# moth_v3_60mm_v3_0.net
KiCad netlist of a schematic drawn in EAGLE
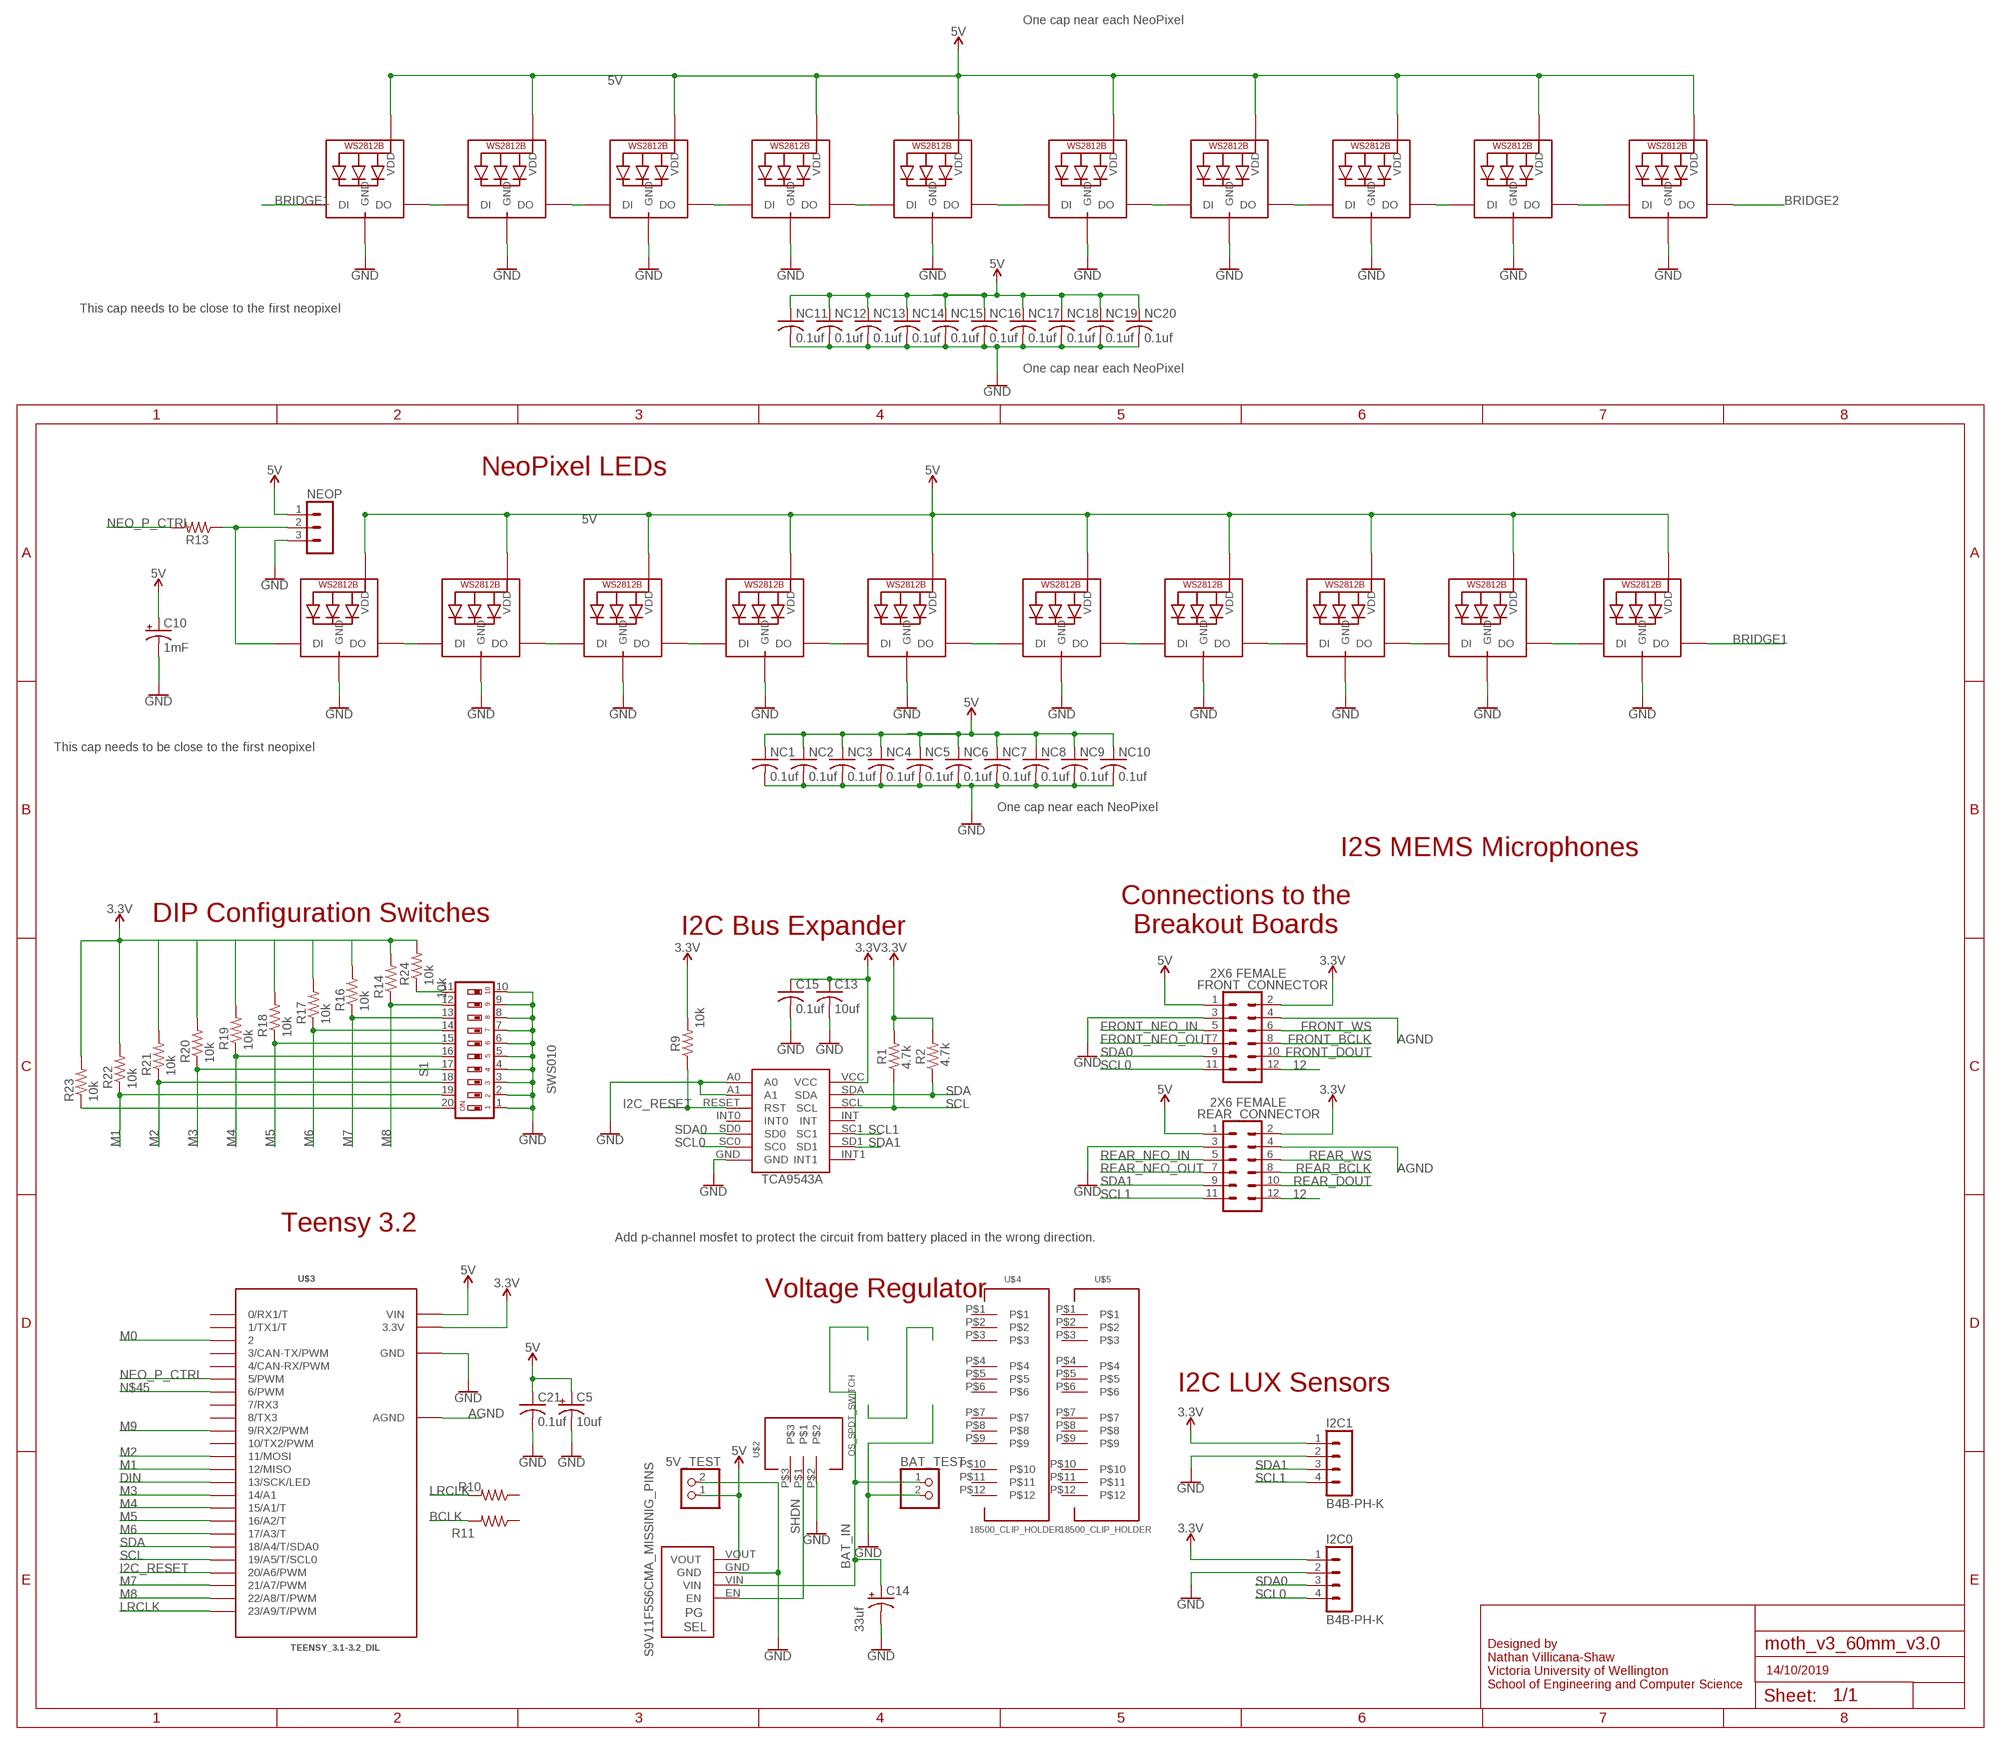
[diagram p0: schematic, sheet 1]

(export (version "E")
  (design (tool "Eeschema 10.0.6"))
  (components
    (comp (ref "5V_TEST")
      (value "PINHD-1X2")
      (footprint "eagle-import:1X02")
      (libsource (lib "eagle-import") (part "PINHD-1X2"))
    )
    (comp (ref "BAT_TEST")
      (value "PINHD-1X2")
      (footprint "eagle-import:1X02")
      (libsource (lib "eagle-import") (part "PINHD-1X2"))
    )
    (comp (ref "C5")
      (value "10uf")
      (footprint "eagle-import:E2,5-6")
      (libsource (lib "eagle-import") (part "CPOL-USE2.5-6"))
    )
    (comp (ref "C10")
      (value "1mF")
      (footprint "eagle-import:CPOL-RADIAL-5MM-10MM")
      (libsource (lib "eagle-import") (part "1000UF-RADIAL-5MM-25V-20%"))
    )
    (comp (ref "C13")
      (value "10uf")
      (footprint "eagle-import:C1206K")
      (libsource (lib "eagle-import") (part "C-USC1206K"))
    )
    (comp (ref "C14")
      (value "33uf")
      (footprint "eagle-import:E2-5")
      (libsource (lib "eagle-import") (part "CPOL-USE2-5"))
    )
    (comp (ref "C15")
      (value "0.1uf")
      (footprint "eagle-import:C1206K")
      (libsource (lib "eagle-import") (part "C-USC1206K"))
    )
    (comp (ref "C21")
      (value "0.1uf")
      (footprint "eagle-import:C1206K")
      (libsource (lib "eagle-import") (part "C-USC1206K"))
    )
    (comp (ref "FRONT_CONNECTOR")
      (value "2X6 FEMALE")
      (footprint "eagle-import:2X6")
      (libsource (lib "eagle-import") (part "CONN_06X2PTH_FEMALE"))
    )
    (comp (ref "I2C0")
      (value "B4B-PH-K")
      (footprint "eagle-import:B4B-PH-K")
      (libsource (lib "eagle-import") (part "B4B-PH-K"))
    )
    (comp (ref "I2C1")
      (value "B4B-PH-K")
      (footprint "eagle-import:B4B-PH-K")
      (libsource (lib "eagle-import") (part "B4B-PH-K"))
    )
    (comp (ref "NC1")
      (value "0.1uf")
      (footprint "eagle-import:C1206K")
      (libsource (lib "eagle-import") (part "C-USC1206K"))
    )
    (comp (ref "NC2")
      (value "0.1uf")
      (footprint "eagle-import:C1206K")
      (libsource (lib "eagle-import") (part "C-USC1206K"))
    )
    (comp (ref "NC3")
      (value "0.1uf")
      (footprint "eagle-import:C1206K")
      (libsource (lib "eagle-import") (part "C-USC1206K"))
    )
    (comp (ref "NC4")
      (value "0.1uf")
      (footprint "eagle-import:C1206K")
      (libsource (lib "eagle-import") (part "C-USC1206K"))
    )
    (comp (ref "NC5")
      (value "0.1uf")
      (footprint "eagle-import:C1206K")
      (libsource (lib "eagle-import") (part "C-USC1206K"))
    )
    (comp (ref "NC6")
      (value "0.1uf")
      (footprint "eagle-import:C1206K")
      (libsource (lib "eagle-import") (part "C-USC1206K"))
    )
    (comp (ref "NC7")
      (value "0.1uf")
      (footprint "eagle-import:C1206K")
      (libsource (lib "eagle-import") (part "C-USC1206K"))
    )
    (comp (ref "NC8")
      (value "0.1uf")
      (footprint "eagle-import:C1206K")
      (libsource (lib "eagle-import") (part "C-USC1206K"))
    )
    (comp (ref "NC9")
      (value "0.1uf")
      (footprint "eagle-import:C1206K")
      (libsource (lib "eagle-import") (part "C-USC1206K"))
    )
    (comp (ref "NC10")
      (value "0.1uf")
      (footprint "eagle-import:C1206K")
      (libsource (lib "eagle-import") (part "C-USC1206K"))
    )
    (comp (ref "NC11")
      (value "0.1uf")
      (footprint "eagle-import:C1206K")
      (libsource (lib "eagle-import") (part "C-USC1206K"))
    )
    (comp (ref "NC12")
      (value "0.1uf")
      (footprint "eagle-import:C1206K")
      (libsource (lib "eagle-import") (part "C-USC1206K"))
    )
    (comp (ref "NC13")
      (value "0.1uf")
      (footprint "eagle-import:C1206K")
      (libsource (lib "eagle-import") (part "C-USC1206K"))
    )
    (comp (ref "NC14")
      (value "0.1uf")
      (footprint "eagle-import:C1206K")
      (libsource (lib "eagle-import") (part "C-USC1206K"))
    )
    (comp (ref "NC15")
      (value "0.1uf")
      (footprint "eagle-import:C1206K")
      (libsource (lib "eagle-import") (part "C-USC1206K"))
    )
    (comp (ref "NC16")
      (value "0.1uf")
      (footprint "eagle-import:C1206K")
      (libsource (lib "eagle-import") (part "C-USC1206K"))
    )
    (comp (ref "NC17")
      (value "0.1uf")
      (footprint "eagle-import:C1206K")
      (libsource (lib "eagle-import") (part "C-USC1206K"))
    )
    (comp (ref "NC18")
      (value "0.1uf")
      (footprint "eagle-import:C1206K")
      (libsource (lib "eagle-import") (part "C-USC1206K"))
    )
    (comp (ref "NC19")
      (value "0.1uf")
      (footprint "eagle-import:C1206K")
      (libsource (lib "eagle-import") (part "C-USC1206K"))
    )
    (comp (ref "NC20")
      (value "0.1uf")
      (footprint "eagle-import:C1206K")
      (libsource (lib "eagle-import") (part "C-USC1206K"))
    )
    (comp (ref "NEO1")
      (value "WS2812B5050")
      (footprint "eagle-import:WS2812B")
      (libsource (lib "eagle-import") (part "WS2812B5050"))
    )
    (comp (ref "NEO2")
      (value "WS2812B5050")
      (footprint "eagle-import:WS2812B")
      (libsource (lib "eagle-import") (part "WS2812B5050"))
    )
    (comp (ref "NEO3")
      (value "WS2812B5050")
      (footprint "eagle-import:WS2812B")
      (libsource (lib "eagle-import") (part "WS2812B5050"))
    )
    (comp (ref "NEO4")
      (value "WS2812B5050")
      (footprint "eagle-import:WS2812B")
      (libsource (lib "eagle-import") (part "WS2812B5050"))
    )
    (comp (ref "NEO5")
      (value "WS2812B5050")
      (footprint "eagle-import:WS2812B")
      (libsource (lib "eagle-import") (part "WS2812B5050"))
    )
    (comp (ref "NEO6")
      (value "WS2812B5050")
      (footprint "eagle-import:WS2812B")
      (libsource (lib "eagle-import") (part "WS2812B5050"))
    )
    (comp (ref "NEO7")
      (value "WS2812B5050")
      (footprint "eagle-import:WS2812B")
      (libsource (lib "eagle-import") (part "WS2812B5050"))
    )
    (comp (ref "NEO8")
      (value "WS2812B5050")
      (footprint "eagle-import:WS2812B")
      (libsource (lib "eagle-import") (part "WS2812B5050"))
    )
    (comp (ref "NEO9")
      (value "WS2812B5050")
      (footprint "eagle-import:WS2812B")
      (libsource (lib "eagle-import") (part "WS2812B5050"))
    )
    (comp (ref "NEO10")
      (value "WS2812B5050")
      (footprint "eagle-import:WS2812B")
      (libsource (lib "eagle-import") (part "WS2812B5050"))
    )
    (comp (ref "NEO11")
      (value "WS2812B5050")
      (footprint "eagle-import:WS2812B")
      (libsource (lib "eagle-import") (part "WS2812B5050"))
    )
    (comp (ref "NEO12")
      (value "WS2812B5050")
      (footprint "eagle-import:WS2812B")
      (libsource (lib "eagle-import") (part "WS2812B5050"))
    )
    (comp (ref "NEO13")
      (value "WS2812B5050")
      (footprint "eagle-import:WS2812B")
      (libsource (lib "eagle-import") (part "WS2812B5050"))
    )
    (comp (ref "NEO14")
      (value "WS2812B5050")
      (footprint "eagle-import:WS2812B")
      (libsource (lib "eagle-import") (part "WS2812B5050"))
    )
    (comp (ref "NEO15")
      (value "WS2812B5050")
      (footprint "eagle-import:WS2812B")
      (libsource (lib "eagle-import") (part "WS2812B5050"))
    )
    (comp (ref "NEO16")
      (value "WS2812B5050")
      (footprint "eagle-import:WS2812B")
      (libsource (lib "eagle-import") (part "WS2812B5050"))
    )
    (comp (ref "NEO17")
      (value "WS2812B5050")
      (footprint "eagle-import:WS2812B")
      (libsource (lib "eagle-import") (part "WS2812B5050"))
    )
    (comp (ref "NEO18")
      (value "WS2812B5050")
      (footprint "eagle-import:WS2812B")
      (libsource (lib "eagle-import") (part "WS2812B5050"))
    )
    (comp (ref "NEO19")
      (value "WS2812B5050")
      (footprint "eagle-import:WS2812B")
      (libsource (lib "eagle-import") (part "WS2812B5050"))
    )
    (comp (ref "NEO20")
      (value "WS2812B5050")
      (footprint "eagle-import:WS2812B")
      (libsource (lib "eagle-import") (part "WS2812B5050"))
    )
    (comp (ref "NEOP")
      (value "B3B-PH-K")
      (footprint "eagle-import:B3B-PH-K")
      (libsource (lib "eagle-import") (part "B3B-PH-K"))
    )
    (comp (ref "R1")
      (value "4.7k")
      (footprint "eagle-import:R1206W")
      (libsource (lib "eagle-import") (part "R-US_R1206W"))
    )
    (comp (ref "R2")
      (value "4.7k")
      (footprint "eagle-import:R1206W")
      (libsource (lib "eagle-import") (part "R-US_R1206W"))
    )
    (comp (ref "R9")
      (value "10k")
      (footprint "eagle-import:R1206W")
      (libsource (lib "eagle-import") (part "R-US_R1206W"))
    )
    (comp (ref "R10")
      (value "68R")
      (footprint "eagle-import:M1206")
      (libsource (lib "eagle-import") (part "R-US_M1206"))
    )
    (comp (ref "R11")
      (value "68R")
      (footprint "eagle-import:M1206")
      (libsource (lib "eagle-import") (part "R-US_M1206"))
    )
    (comp (ref "R13")
      (value "300 R")
      (footprint "eagle-import:R1206W")
      (libsource (lib "eagle-import") (part "R-US_R1206W"))
    )
    (comp (ref "R14")
      (value "10k")
      (footprint "eagle-import:R1206W")
      (libsource (lib "eagle-import") (part "R-US_R1206W"))
    )
    (comp (ref "R16")
      (value "10k")
      (footprint "eagle-import:R1206W")
      (libsource (lib "eagle-import") (part "R-US_R1206W"))
    )
    (comp (ref "R17")
      (value "10k")
      (footprint "eagle-import:R1206W")
      (libsource (lib "eagle-import") (part "R-US_R1206W"))
    )
    (comp (ref "R18")
      (value "10k")
      (footprint "eagle-import:R1206W")
      (libsource (lib "eagle-import") (part "R-US_R1206W"))
    )
    (comp (ref "R19")
      (value "10k")
      (footprint "eagle-import:R1206W")
      (libsource (lib "eagle-import") (part "R-US_R1206W"))
    )
    (comp (ref "R20")
      (value "10k")
      (footprint "eagle-import:R1206W")
      (libsource (lib "eagle-import") (part "R-US_R1206W"))
    )
    (comp (ref "R21")
      (value "10k")
      (footprint "eagle-import:R1206W")
      (libsource (lib "eagle-import") (part "R-US_R1206W"))
    )
    (comp (ref "R22")
      (value "10k")
      (footprint "eagle-import:R1206W")
      (libsource (lib "eagle-import") (part "R-US_R1206W"))
    )
    (comp (ref "R23")
      (value "10k")
      (footprint "eagle-import:R1206W")
      (libsource (lib "eagle-import") (part "R-US_R1206W"))
    )
    (comp (ref "R24")
      (value "10k")
      (footprint "eagle-import:R1206W")
      (libsource (lib "eagle-import") (part "R-US_R1206W"))
    )
    (comp (ref "REAR_CONNECTOR")
      (value "2X6 FEMALE")
      (footprint "eagle-import:2X6")
      (libsource (lib "eagle-import") (part "CONN_06X2PTH_FEMALE"))
    )
    (comp (ref "S1")
      (value "SWS010")
      (footprint "eagle-import:SMS-010")
      (libsource (lib "eagle-import") (part "SWS010"))
    )
    (comp (ref "U$1")
      (value "TCA9543A")
      (footprint "eagle-import:SO14")
      (libsource (lib "eagle-import") (part "TCA9543A"))
    )
    (comp (ref "U$2")
      (value "OS_SPDT_SWITCH")
      (footprint "eagle-import:OS_SPDT_SLIDE_SWITCH")
      (libsource (lib "eagle-import") (part "OS_SPDT_SWITCH"))
    )
    (comp (ref "U$3")
      (value "TEENSY_3.1-3.2_DIL")
      (footprint "eagle-import:TEENSY_3.0-3.2&LC_DIL")
      (libsource (lib "eagle-import") (part "TEENSY_3.1-3.2_DIL"))
    )
    (comp (ref "U$4")
      (value "18500_CLIP_HOLDER")
      (footprint "eagle-import:3PINBATTERY_CLIP")
      (libsource (lib "eagle-import") (part "18500_CLIP_HOLDER"))
    )
    (comp (ref "U$5")
      (value "18500_CLIP_HOLDER")
      (footprint "eagle-import:3PINBATTERY_CLIP")
      (libsource (lib "eagle-import") (part "18500_CLIP_HOLDER"))
    )
    (comp (ref "U$6")
      (value "S9V11F5S6CMA_MISSINIG_PINS")
      (footprint "eagle-import:S9V11F3S5CMA_MISSING_PINS")
      (libsource (lib "eagle-import") (part "S9V11F5S6CMA_MISSINIG_PINS"))
    )
  )
  (nets
    (net (code "1") (name "/12") (class "Default")
      (node (ref "FRONT_CONNECTOR") (pin "12") (pinfunction "12_12") (pintype "passive"))
      (node (ref "REAR_CONNECTOR") (pin "12") (pinfunction "12_12") (pintype "passive"))
    )
    (net (code "2") (name "/AGND") (class "Default")
      (node (ref "FRONT_CONNECTOR") (pin "4") (pinfunction "4_4") (pintype "passive"))
      (node (ref "REAR_CONNECTOR") (pin "4") (pinfunction "4_4") (pintype "passive"))
      (node (ref "U$3") (pin "AGND") (pinfunction "AGND_AGND") (pintype "power_in"))
    )
    (net (code "3") (name "/BAT_IN") (class "Default")
      (node (ref "BAT_TEST") (pin "1") (pinfunction "1_1") (pintype "passive"))
      (node (ref "C14") (pin "+") (pinfunction "+_+") (pintype "passive"))
      (node (ref "U$6") (pin "VIN") (pinfunction "VIN_VIN") (pintype "bidirectional"))
    )
    (net (code "4") (name "/BCLK") (class "Default")
      (node (ref "R11") (pin "2") (pinfunction "2_2") (pintype "passive"))
    )
    (net (code "5") (name "/BRIDGE1") (class "Default")
      (node (ref "NEO10") (pin "2-DOUT") (pinfunction "DO_2-DOUT") (pintype "output"))
      (node (ref "NEO14") (pin "4-DIN") (pinfunction "DI_4-DIN") (pintype "input"))
    )
    (net (code "6") (name "/BRIDGE2") (class "Default")
      (node (ref "NEO20") (pin "2-DOUT") (pinfunction "DO_2-DOUT") (pintype "output"))
    )
    (net (code "7") (name "/DIN") (class "Default")
      (node (ref "U$3") (pin "13") (pinfunction "13/SCK/LED_13") (pintype "bidirectional"))
    )
    (net (code "8") (name "/FRONT_BCLK") (class "Default")
      (node (ref "FRONT_CONNECTOR") (pin "8") (pinfunction "8_8") (pintype "passive"))
    )
    (net (code "9") (name "/FRONT_DOUT") (class "Default")
      (node (ref "FRONT_CONNECTOR") (pin "10") (pinfunction "10_10") (pintype "passive"))
    )
    (net (code "10") (name "/FRONT_NEO_IN") (class "Default")
      (node (ref "FRONT_CONNECTOR") (pin "5") (pinfunction "5_5") (pintype "passive"))
    )
    (net (code "11") (name "/FRONT_NEO_OUT") (class "Default")
      (node (ref "FRONT_CONNECTOR") (pin "7") (pinfunction "7_7") (pintype "passive"))
    )
    (net (code "12") (name "/FRONT_WS") (class "Default")
      (node (ref "FRONT_CONNECTOR") (pin "6") (pinfunction "6_6") (pintype "passive"))
    )
    (net (code "13") (name "/I2C_RESET") (class "Default")
      (node (ref "R9") (pin "1") (pinfunction "1_1") (pintype "passive"))
      (node (ref "U$1") (pin "RESET") (pinfunction "RST_RESET") (pintype "bidirectional"))
      (node (ref "U$3") (pin "20/A6") (pinfunction "20/A6/PWM_20/A6") (pintype "bidirectional"))
    )
    (net (code "14") (name "/LRCLK") (class "Default")
      (node (ref "R10") (pin "2") (pinfunction "2_2") (pintype "passive"))
      (node (ref "U$3") (pin "23/A9") (pinfunction "23/A9/T/PWM_23/A9") (pintype "bidirectional"))
    )
    (net (code "15") (name "/M0") (class "Default")
      (node (ref "U$3") (pin "2") (pinfunction "2_2") (pintype "bidirectional"))
    )
    (net (code "16") (name "/M1") (class "Default")
      (node (ref "R22") (pin "1") (pinfunction "1_1") (pintype "passive"))
      (node (ref "S1") (pin "19") (pinfunction "19_19") (pintype "passive"))
      (node (ref "U$3") (pin "12") (pinfunction "12/MISO_12") (pintype "bidirectional"))
    )
    (net (code "17") (name "/M2") (class "Default")
      (node (ref "R21") (pin "1") (pinfunction "1_1") (pintype "passive"))
      (node (ref "S1") (pin "18") (pinfunction "18_18") (pintype "passive"))
      (node (ref "U$3") (pin "11") (pinfunction "11/MOSI_11") (pintype "bidirectional"))
    )
    (net (code "18") (name "/M3") (class "Default")
      (node (ref "R20") (pin "1") (pinfunction "1_1") (pintype "passive"))
      (node (ref "S1") (pin "17") (pinfunction "17_17") (pintype "passive"))
      (node (ref "U$3") (pin "14/A0") (pinfunction "14/A1_14/A0") (pintype "bidirectional"))
    )
    (net (code "19") (name "/M4") (class "Default")
      (node (ref "R19") (pin "1") (pinfunction "1_1") (pintype "passive"))
      (node (ref "S1") (pin "16") (pinfunction "16_16") (pintype "passive"))
      (node (ref "U$3") (pin "15/A1") (pinfunction "15/A1/T_15/A1") (pintype "bidirectional"))
    )
    (net (code "20") (name "/M5") (class "Default")
      (node (ref "R18") (pin "1") (pinfunction "1_1") (pintype "passive"))
      (node (ref "S1") (pin "15") (pinfunction "15_15") (pintype "passive"))
      (node (ref "U$3") (pin "16/A2") (pinfunction "16/A2/T_16/A2") (pintype "bidirectional"))
    )
    (net (code "21") (name "/M6") (class "Default")
      (node (ref "R17") (pin "1") (pinfunction "1_1") (pintype "passive"))
      (node (ref "S1") (pin "14") (pinfunction "14_14") (pintype "passive"))
      (node (ref "U$3") (pin "17/A3") (pinfunction "17/A3/T_17/A3") (pintype "bidirectional"))
    )
    (net (code "22") (name "/M7") (class "Default")
      (node (ref "R16") (pin "1") (pinfunction "1_1") (pintype "passive"))
      (node (ref "S1") (pin "13") (pinfunction "13_13") (pintype "passive"))
      (node (ref "U$3") (pin "21/A7") (pinfunction "21/A7/PWM_21/A7") (pintype "bidirectional"))
    )
    (net (code "23") (name "/M8") (class "Default")
      (node (ref "R14") (pin "1") (pinfunction "1_1") (pintype "passive"))
      (node (ref "S1") (pin "12") (pinfunction "12_12") (pintype "passive"))
      (node (ref "U$3") (pin "22/A8") (pinfunction "22/A8/T/PWM_22/A8") (pintype "bidirectional"))
    )
    (net (code "24") (name "/M9") (class "Default")
      (node (ref "U$3") (pin "9") (pinfunction "9/RX2/PWM_9") (pintype "bidirectional"))
    )
    (net (code "25") (name "/N$45") (class "Default")
      (node (ref "U$3") (pin "6") (pinfunction "6/PWM_6") (pintype "bidirectional"))
    )
    (net (code "26") (name "/NEO_P_CTRL") (class "Default")
      (node (ref "R13") (pin "2") (pinfunction "2_2") (pintype "passive"))
      (node (ref "U$3") (pin "5") (pinfunction "5/PWM_5") (pintype "bidirectional"))
    )
    (net (code "27") (name "/REAR_BCLK") (class "Default")
      (node (ref "REAR_CONNECTOR") (pin "8") (pinfunction "8_8") (pintype "passive"))
    )
    (net (code "28") (name "/REAR_DOUT") (class "Default")
      (node (ref "REAR_CONNECTOR") (pin "10") (pinfunction "10_10") (pintype "passive"))
    )
    (net (code "29") (name "/REAR_NEO_IN") (class "Default")
      (node (ref "REAR_CONNECTOR") (pin "5") (pinfunction "5_5") (pintype "passive"))
    )
    (net (code "30") (name "/REAR_NEO_OUT") (class "Default")
      (node (ref "REAR_CONNECTOR") (pin "7") (pinfunction "7_7") (pintype "passive"))
    )
    (net (code "31") (name "/REAR_WS") (class "Default")
      (node (ref "REAR_CONNECTOR") (pin "6") (pinfunction "6_6") (pintype "passive"))
    )
    (net (code "32") (name "/SCL") (class "Default")
      (node (ref "R1") (pin "1") (pinfunction "1_1") (pintype "passive"))
      (node (ref "U$1") (pin "SCL") (pinfunction "SCL_SCL") (pintype "bidirectional"))
      (node (ref "U$3") (pin "19/A5") (pinfunction "19/A5/T/SCL0_19/A5") (pintype "bidirectional"))
    )
    (net (code "33") (name "/SCL0") (class "Default")
      (node (ref "FRONT_CONNECTOR") (pin "11") (pinfunction "11_11") (pintype "passive"))
      (node (ref "I2C0") (pin "4") (pinfunction "4_4") (pintype "passive"))
      (node (ref "U$1") (pin "SC0") (pinfunction "SC0_SC0") (pintype "bidirectional"))
    )
    (net (code "34") (name "/SCL1") (class "Default")
      (node (ref "I2C1") (pin "4") (pinfunction "4_4") (pintype "passive"))
      (node (ref "REAR_CONNECTOR") (pin "11") (pinfunction "11_11") (pintype "passive"))
      (node (ref "U$1") (pin "SC1") (pinfunction "SC1_SC1") (pintype "bidirectional"))
    )
    (net (code "35") (name "/SDA") (class "Default")
      (node (ref "R2") (pin "1") (pinfunction "1_1") (pintype "passive"))
      (node (ref "U$1") (pin "SDA") (pinfunction "SDA_SDA") (pintype "bidirectional"))
      (node (ref "U$3") (pin "18/A4") (pinfunction "18/A4/T/SDA0_18/A4") (pintype "bidirectional"))
    )
    (net (code "36") (name "/SDA0") (class "Default")
      (node (ref "FRONT_CONNECTOR") (pin "9") (pinfunction "9_9") (pintype "passive"))
      (node (ref "I2C0") (pin "3") (pinfunction "3_3") (pintype "passive"))
      (node (ref "U$1") (pin "SD0") (pinfunction "SD0_SD0") (pintype "bidirectional"))
    )
    (net (code "37") (name "/SDA1") (class "Default")
      (node (ref "I2C1") (pin "3") (pinfunction "3_3") (pintype "passive"))
      (node (ref "REAR_CONNECTOR") (pin "9") (pinfunction "9_9") (pintype "passive"))
      (node (ref "U$1") (pin "SD1") (pinfunction "SD1_SD1") (pintype "bidirectional"))
    )
    (net (code "38") (name "/SHDN") (class "Default")
      (node (ref "U$2") (pin "P$1") (pinfunction "P$1_P$1") (pintype "bidirectional"))
      (node (ref "U$6") (pin "EN") (pinfunction "EN_EN") (pintype "bidirectional"))
    )
    (net (code "39") (name "3.3V") (class "Default")
      (node (ref "C13") (pin "1") (pinfunction "1_1") (pintype "passive"))
      (node (ref "C15") (pin "1") (pinfunction "1_1") (pintype "passive"))
      (node (ref "FRONT_CONNECTOR") (pin "2") (pinfunction "2_2") (pintype "passive"))
      (node (ref "I2C0") (pin "1") (pinfunction "1_1") (pintype "passive"))
      (node (ref "I2C1") (pin "1") (pinfunction "1_1") (pintype "passive"))
      (node (ref "R1") (pin "2") (pinfunction "2_2") (pintype "passive"))
      (node (ref "R14") (pin "2") (pinfunction "2_2") (pintype "passive"))
      (node (ref "R2") (pin "2") (pinfunction "2_2") (pintype "passive"))
      (node (ref "R22") (pin "2") (pinfunction "2_2") (pintype "passive"))
      (node (ref "R23") (pin "2") (pinfunction "2_2") (pintype "passive"))
      (node (ref "R24") (pin "2") (pinfunction "2_2") (pintype "passive"))
      (node (ref "R9") (pin "2") (pinfunction "2_2") (pintype "passive"))
      (node (ref "REAR_CONNECTOR") (pin "2") (pinfunction "2_2") (pintype "passive"))
      (node (ref "U$1") (pin "VCC") (pinfunction "VCC_VCC") (pintype "bidirectional"))
      (node (ref "U$3") (pin "3.3V") (pinfunction "3.3V_3.3V") (pintype "power_in"))
    )
    (net (code "40") (name "5V") (class "Default")
      (node (ref "5V_TEST") (pin "1") (pinfunction "1_1") (pintype "passive"))
      (node (ref "C10") (pin "+") (pinfunction "+_+") (pintype "passive"))
      (node (ref "C21") (pin "1") (pinfunction "1_1") (pintype "passive"))
      (node (ref "C5") (pin "+") (pinfunction "+_+") (pintype "passive"))
      (node (ref "FRONT_CONNECTOR") (pin "1") (pinfunction "1_1") (pintype "passive"))
      (node (ref "NC1") (pin "1") (pinfunction "1_1") (pintype "passive"))
      (node (ref "NC10") (pin "1") (pinfunction "1_1") (pintype "passive"))
      (node (ref "NC11") (pin "1") (pinfunction "1_1") (pintype "passive"))
      (node (ref "NC12") (pin "1") (pinfunction "1_1") (pintype "passive"))
      (node (ref "NC13") (pin "1") (pinfunction "1_1") (pintype "passive"))
      (node (ref "NC14") (pin "1") (pinfunction "1_1") (pintype "passive"))
      (node (ref "NC15") (pin "1") (pinfunction "1_1") (pintype "passive"))
      (node (ref "NC16") (pin "1") (pinfunction "1_1") (pintype "passive"))
      (node (ref "NC17") (pin "1") (pinfunction "1_1") (pintype "passive"))
      (node (ref "NC18") (pin "1") (pinfunction "1_1") (pintype "passive"))
      (node (ref "NC19") (pin "1") (pinfunction "1_1") (pintype "passive"))
      (node (ref "NC2") (pin "1") (pinfunction "1_1") (pintype "passive"))
      (node (ref "NC20") (pin "1") (pinfunction "1_1") (pintype "passive"))
      (node (ref "NC3") (pin "1") (pinfunction "1_1") (pintype "passive"))
      (node (ref "NC4") (pin "1") (pinfunction "1_1") (pintype "passive"))
      (node (ref "NC5") (pin "1") (pinfunction "1_1") (pintype "passive"))
      (node (ref "NC6") (pin "1") (pinfunction "1_1") (pintype "passive"))
      (node (ref "NC7") (pin "1") (pinfunction "1_1") (pintype "passive"))
      (node (ref "NC8") (pin "1") (pinfunction "1_1") (pintype "passive"))
      (node (ref "NC9") (pin "1") (pinfunction "1_1") (pintype "passive"))
      (node (ref "NEO1") (pin "1-VDD") (pinfunction "VDD_1-VDD") (pintype "power_in"))
      (node (ref "NEO10") (pin "1-VDD") (pinfunction "VDD_1-VDD") (pintype "power_in"))
      (node (ref "NEO11") (pin "1-VDD") (pinfunction "VDD_1-VDD") (pintype "power_in"))
      (node (ref "NEO12") (pin "1-VDD") (pinfunction "VDD_1-VDD") (pintype "power_in"))
      (node (ref "NEO13") (pin "1-VDD") (pinfunction "VDD_1-VDD") (pintype "power_in"))
      (node (ref "NEO14") (pin "1-VDD") (pinfunction "VDD_1-VDD") (pintype "power_in"))
      (node (ref "NEO15") (pin "1-VDD") (pinfunction "VDD_1-VDD") (pintype "power_in"))
      (node (ref "NEO16") (pin "1-VDD") (pinfunction "VDD_1-VDD") (pintype "power_in"))
      (node (ref "NEO17") (pin "1-VDD") (pinfunction "VDD_1-VDD") (pintype "power_in"))
      (node (ref "NEO18") (pin "1-VDD") (pinfunction "VDD_1-VDD") (pintype "power_in"))
      (node (ref "NEO19") (pin "1-VDD") (pinfunction "VDD_1-VDD") (pintype "power_in"))
      (node (ref "NEO2") (pin "1-VDD") (pinfunction "VDD_1-VDD") (pintype "power_in"))
      (node (ref "NEO20") (pin "1-VDD") (pinfunction "VDD_1-VDD") (pintype "power_in"))
      (node (ref "NEO3") (pin "1-VDD") (pinfunction "VDD_1-VDD") (pintype "power_in"))
      (node (ref "NEO4") (pin "1-VDD") (pinfunction "VDD_1-VDD") (pintype "power_in"))
      (node (ref "NEO5") (pin "1-VDD") (pinfunction "VDD_1-VDD") (pintype "power_in"))
      (node (ref "NEO6") (pin "1-VDD") (pinfunction "VDD_1-VDD") (pintype "power_in"))
      (node (ref "NEO7") (pin "1-VDD") (pinfunction "VDD_1-VDD") (pintype "power_in"))
      (node (ref "NEO8") (pin "1-VDD") (pinfunction "VDD_1-VDD") (pintype "power_in"))
      (node (ref "NEO9") (pin "1-VDD") (pinfunction "VDD_1-VDD") (pintype "power_in"))
      (node (ref "NEOP") (pin "1") (pinfunction "1_1") (pintype "passive"))
      (node (ref "REAR_CONNECTOR") (pin "1") (pinfunction "1_1") (pintype "passive"))
      (node (ref "U$3") (pin "VIN") (pinfunction "VIN_VIN") (pintype "power_in"))
      (node (ref "U$6") (pin "VOUT") (pinfunction "VOUT_VOUT") (pintype "bidirectional"))
    )
    (net (code "41") (name "GND") (class "Default")
      (node (ref "5V_TEST") (pin "2") (pinfunction "2_2") (pintype "passive"))
      (node (ref "BAT_TEST") (pin "2") (pinfunction "2_2") (pintype "passive"))
      (node (ref "C10") (pin "-") (pinfunction "-_-") (pintype "passive"))
      (node (ref "C13") (pin "2") (pinfunction "2_2") (pintype "passive"))
      (node (ref "C14") (pin "-") (pinfunction "-_-") (pintype "passive"))
      (node (ref "C15") (pin "2") (pinfunction "2_2") (pintype "passive"))
      (node (ref "C21") (pin "2") (pinfunction "2_2") (pintype "passive"))
      (node (ref "C5") (pin "-") (pinfunction "-_-") (pintype "passive"))
      (node (ref "FRONT_CONNECTOR") (pin "3") (pinfunction "3_3") (pintype "passive"))
      (node (ref "I2C0") (pin "2") (pinfunction "2_2") (pintype "passive"))
      (node (ref "I2C1") (pin "2") (pinfunction "2_2") (pintype "passive"))
      (node (ref "NC1") (pin "2") (pinfunction "2_2") (pintype "passive"))
      (node (ref "NC10") (pin "2") (pinfunction "2_2") (pintype "passive"))
      (node (ref "NC11") (pin "2") (pinfunction "2_2") (pintype "passive"))
      (node (ref "NC12") (pin "2") (pinfunction "2_2") (pintype "passive"))
      (node (ref "NC13") (pin "2") (pinfunction "2_2") (pintype "passive"))
      (node (ref "NC14") (pin "2") (pinfunction "2_2") (pintype "passive"))
      (node (ref "NC15") (pin "2") (pinfunction "2_2") (pintype "passive"))
      (node (ref "NC16") (pin "2") (pinfunction "2_2") (pintype "passive"))
      (node (ref "NC17") (pin "2") (pinfunction "2_2") (pintype "passive"))
      (node (ref "NC18") (pin "2") (pinfunction "2_2") (pintype "passive"))
      (node (ref "NC19") (pin "2") (pinfunction "2_2") (pintype "passive"))
      (node (ref "NC2") (pin "2") (pinfunction "2_2") (pintype "passive"))
      (node (ref "NC20") (pin "2") (pinfunction "2_2") (pintype "passive"))
      (node (ref "NC3") (pin "2") (pinfunction "2_2") (pintype "passive"))
      (node (ref "NC4") (pin "2") (pinfunction "2_2") (pintype "passive"))
      (node (ref "NC5") (pin "2") (pinfunction "2_2") (pintype "passive"))
      (node (ref "NC6") (pin "2") (pinfunction "2_2") (pintype "passive"))
      (node (ref "NC7") (pin "2") (pinfunction "2_2") (pintype "passive"))
      (node (ref "NC8") (pin "2") (pinfunction "2_2") (pintype "passive"))
      (node (ref "NC9") (pin "2") (pinfunction "2_2") (pintype "passive"))
      (node (ref "NEO1") (pin "3-GND") (pinfunction "GND_3-GND") (pintype "power_in"))
      (node (ref "NEO10") (pin "3-GND") (pinfunction "GND_3-GND") (pintype "power_in"))
      (node (ref "NEO11") (pin "3-GND") (pinfunction "GND_3-GND") (pintype "power_in"))
      (node (ref "NEO12") (pin "3-GND") (pinfunction "GND_3-GND") (pintype "power_in"))
      (node (ref "NEO13") (pin "3-GND") (pinfunction "GND_3-GND") (pintype "power_in"))
      (node (ref "NEO14") (pin "3-GND") (pinfunction "GND_3-GND") (pintype "power_in"))
      (node (ref "NEO15") (pin "3-GND") (pinfunction "GND_3-GND") (pintype "power_in"))
      (node (ref "NEO16") (pin "3-GND") (pinfunction "GND_3-GND") (pintype "power_in"))
      (node (ref "NEO17") (pin "3-GND") (pinfunction "GND_3-GND") (pintype "power_in"))
      (node (ref "NEO18") (pin "3-GND") (pinfunction "GND_3-GND") (pintype "power_in"))
      (node (ref "NEO19") (pin "3-GND") (pinfunction "GND_3-GND") (pintype "power_in"))
      (node (ref "NEO2") (pin "3-GND") (pinfunction "GND_3-GND") (pintype "power_in"))
      (node (ref "NEO20") (pin "3-GND") (pinfunction "GND_3-GND") (pintype "power_in"))
      (node (ref "NEO3") (pin "3-GND") (pinfunction "GND_3-GND") (pintype "power_in"))
      (node (ref "NEO4") (pin "3-GND") (pinfunction "GND_3-GND") (pintype "power_in"))
      (node (ref "NEO5") (pin "3-GND") (pinfunction "GND_3-GND") (pintype "power_in"))
      (node (ref "NEO6") (pin "3-GND") (pinfunction "GND_3-GND") (pintype "power_in"))
      (node (ref "NEO7") (pin "3-GND") (pinfunction "GND_3-GND") (pintype "power_in"))
      (node (ref "NEO8") (pin "3-GND") (pinfunction "GND_3-GND") (pintype "power_in"))
      (node (ref "NEO9") (pin "3-GND") (pinfunction "GND_3-GND") (pintype "power_in"))
      (node (ref "NEOP") (pin "3") (pinfunction "3_3") (pintype "passive"))
      (node (ref "REAR_CONNECTOR") (pin "3") (pinfunction "3_3") (pintype "passive"))
      (node (ref "S1") (pin "1") (pinfunction "1_1") (pintype "passive"))
      (node (ref "S1") (pin "10") (pinfunction "10_10") (pintype "passive"))
      (node (ref "S1") (pin "2") (pinfunction "2_2") (pintype "passive"))
      (node (ref "S1") (pin "3") (pinfunction "3_3") (pintype "passive"))
      (node (ref "S1") (pin "4") (pinfunction "4_4") (pintype "passive"))
      (node (ref "S1") (pin "5") (pinfunction "5_5") (pintype "passive"))
      (node (ref "S1") (pin "6") (pinfunction "6_6") (pintype "passive"))
      (node (ref "S1") (pin "7") (pinfunction "7_7") (pintype "passive"))
      (node (ref "S1") (pin "8") (pinfunction "8_8") (pintype "passive"))
      (node (ref "S1") (pin "9") (pinfunction "9_9") (pintype "passive"))
      (node (ref "U$1") (pin "A0") (pinfunction "A0_A0") (pintype "bidirectional"))
      (node (ref "U$1") (pin "A1") (pinfunction "A1_A1") (pintype "bidirectional"))
      (node (ref "U$1") (pin "GND") (pinfunction "GND_GND") (pintype "bidirectional"))
      (node (ref "U$2") (pin "P$2") (pinfunction "P$2_P$2") (pintype "bidirectional"))
      (node (ref "U$3") (pin "GND") (pinfunction "GND_GND") (pintype "power_in"))
      (node (ref "U$6") (pin "GND") (pinfunction "GND_GND") (pintype "bidirectional"))
    )
    (net (code "42") (name "Net-(NEO1-DI)") (class "Default")
      (node (ref "NEO1") (pin "4-DIN") (pinfunction "DI_4-DIN") (pintype "input"))
      (node (ref "NEOP") (pin "2") (pinfunction "2_2") (pintype "passive"))
      (node (ref "R13") (pin "1") (pinfunction "1_1") (pintype "passive"))
    )
    (net (code "43") (name "Net-(NEO1-DO)") (class "Default")
      (node (ref "NEO1") (pin "2-DOUT") (pinfunction "DO_2-DOUT") (pintype "output"))
      (node (ref "NEO2") (pin "4-DIN") (pinfunction "DI_4-DIN") (pintype "input"))
    )
    (net (code "44") (name "Net-(NEO2-DO)") (class "Default")
      (node (ref "NEO2") (pin "2-DOUT") (pinfunction "DO_2-DOUT") (pintype "output"))
      (node (ref "NEO3") (pin "4-DIN") (pinfunction "DI_4-DIN") (pintype "input"))
    )
    (net (code "45") (name "Net-(NEO3-DO)") (class "Default")
      (node (ref "NEO3") (pin "2-DOUT") (pinfunction "DO_2-DOUT") (pintype "output"))
      (node (ref "NEO4") (pin "4-DIN") (pinfunction "DI_4-DIN") (pintype "input"))
    )
    (net (code "46") (name "Net-(NEO4-DO)") (class "Default")
      (node (ref "NEO4") (pin "2-DOUT") (pinfunction "DO_2-DOUT") (pintype "output"))
      (node (ref "NEO5") (pin "4-DIN") (pinfunction "DI_4-DIN") (pintype "input"))
    )
    (net (code "47") (name "Net-(NEO5-DO)") (class "Default")
      (node (ref "NEO5") (pin "2-DOUT") (pinfunction "DO_2-DOUT") (pintype "output"))
      (node (ref "NEO6") (pin "4-DIN") (pinfunction "DI_4-DIN") (pintype "input"))
    )
    (net (code "48") (name "Net-(NEO6-DO)") (class "Default")
      (node (ref "NEO6") (pin "2-DOUT") (pinfunction "DO_2-DOUT") (pintype "output"))
      (node (ref "NEO7") (pin "4-DIN") (pinfunction "DI_4-DIN") (pintype "input"))
    )
    (net (code "49") (name "Net-(NEO7-DO)") (class "Default")
      (node (ref "NEO7") (pin "2-DOUT") (pinfunction "DO_2-DOUT") (pintype "output"))
      (node (ref "NEO8") (pin "4-DIN") (pinfunction "DI_4-DIN") (pintype "input"))
    )
    (net (code "50") (name "Net-(NEO8-DO)") (class "Default")
      (node (ref "NEO8") (pin "2-DOUT") (pinfunction "DO_2-DOUT") (pintype "output"))
      (node (ref "NEO9") (pin "4-DIN") (pinfunction "DI_4-DIN") (pintype "input"))
    )
    (net (code "51") (name "Net-(NEO10-DI)") (class "Default")
      (node (ref "NEO10") (pin "4-DIN") (pinfunction "DI_4-DIN") (pintype "input"))
      (node (ref "NEO9") (pin "2-DOUT") (pinfunction "DO_2-DOUT") (pintype "output"))
    )
    (net (code "52") (name "Net-(NEO11-DI)") (class "Default")
      (node (ref "NEO11") (pin "4-DIN") (pinfunction "DI_4-DIN") (pintype "input"))
      (node (ref "NEO16") (pin "2-DOUT") (pinfunction "DO_2-DOUT") (pintype "output"))
    )
    (net (code "53") (name "Net-(NEO11-DO)") (class "Default")
      (node (ref "NEO11") (pin "2-DOUT") (pinfunction "DO_2-DOUT") (pintype "output"))
      (node (ref "NEO12") (pin "4-DIN") (pinfunction "DI_4-DIN") (pintype "input"))
    )
    (net (code "54") (name "Net-(NEO12-DO)") (class "Default")
      (node (ref "NEO12") (pin "2-DOUT") (pinfunction "DO_2-DOUT") (pintype "output"))
      (node (ref "NEO13") (pin "4-DIN") (pinfunction "DI_4-DIN") (pintype "input"))
    )
    (net (code "55") (name "Net-(NEO13-DO)") (class "Default")
      (node (ref "NEO13") (pin "2-DOUT") (pinfunction "DO_2-DOUT") (pintype "output"))
      (node (ref "NEO17") (pin "4-DIN") (pinfunction "DI_4-DIN") (pintype "input"))
    )
    (net (code "56") (name "Net-(NEO14-DO)") (class "Default")
      (node (ref "NEO14") (pin "2-DOUT") (pinfunction "DO_2-DOUT") (pintype "output"))
      (node (ref "NEO15") (pin "4-DIN") (pinfunction "DI_4-DIN") (pintype "input"))
    )
    (net (code "57") (name "Net-(NEO15-DO)") (class "Default")
      (node (ref "NEO15") (pin "2-DOUT") (pinfunction "DO_2-DOUT") (pintype "output"))
      (node (ref "NEO16") (pin "4-DIN") (pinfunction "DI_4-DIN") (pintype "input"))
    )
    (net (code "58") (name "Net-(NEO17-DO)") (class "Default")
      (node (ref "NEO17") (pin "2-DOUT") (pinfunction "DO_2-DOUT") (pintype "output"))
      (node (ref "NEO18") (pin "4-DIN") (pinfunction "DI_4-DIN") (pintype "input"))
    )
    (net (code "59") (name "Net-(NEO18-DO)") (class "Default")
      (node (ref "NEO18") (pin "2-DOUT") (pinfunction "DO_2-DOUT") (pintype "output"))
      (node (ref "NEO19") (pin "4-DIN") (pinfunction "DI_4-DIN") (pintype "input"))
    )
    (net (code "60") (name "Net-(NEO19-DO)") (class "Default")
      (node (ref "NEO19") (pin "2-DOUT") (pinfunction "DO_2-DOUT") (pintype "output"))
      (node (ref "NEO20") (pin "4-DIN") (pinfunction "DI_4-DIN") (pintype "input"))
    )
    (net (code "61") (name "Net-(R23-Pad1)") (class "Default")
      (node (ref "R23") (pin "1") (pinfunction "1_1") (pintype "passive"))
      (node (ref "S1") (pin "20") (pinfunction "20_20") (pintype "passive"))
    )
    (net (code "62") (name "Net-(R24-Pad1)") (class "Default")
      (node (ref "R24") (pin "1") (pinfunction "1_1") (pintype "passive"))
      (node (ref "S1") (pin "11") (pinfunction "11_11") (pintype "passive"))
    )
    (net (code "63") (name "unconnected-(R10-Pad1)") (class "Default")
      (node (ref "R10") (pin "1") (pinfunction "1_1") (pintype "passive"))
    )
    (net (code "64") (name "unconnected-(R11-Pad1)") (class "Default")
      (node (ref "R11") (pin "1") (pinfunction "1_1") (pintype "passive"))
    )
    (net (code "65") (name "unconnected-(R16-Pad2)") (class "Default")
      (node (ref "R16") (pin "2") (pinfunction "2_2") (pintype "passive"))
    )
    (net (code "66") (name "unconnected-(R17-Pad2)") (class "Default")
      (node (ref "R17") (pin "2") (pinfunction "2_2") (pintype "passive"))
    )
    (net (code "67") (name "unconnected-(R18-Pad2)") (class "Default")
      (node (ref "R18") (pin "2") (pinfunction "2_2") (pintype "passive"))
    )
    (net (code "68") (name "unconnected-(R19-Pad2)") (class "Default")
      (node (ref "R19") (pin "2") (pinfunction "2_2") (pintype "passive"))
    )
    (net (code "69") (name "unconnected-(R20-Pad2)") (class "Default")
      (node (ref "R20") (pin "2") (pinfunction "2_2") (pintype "passive"))
    )
    (net (code "70") (name "unconnected-(R21-Pad2)") (class "Default")
      (node (ref "R21") (pin "2") (pinfunction "2_2") (pintype "passive"))
    )
    (net (code "71") (name "unconnected-(U$1-PadINT)") (class "Default")
      (node (ref "U$1") (pin "INT") (pinfunction "INT_INT") (pintype "bidirectional"))
    )
    (net (code "72") (name "unconnected-(U$1-PadINT0)") (class "Default")
      (node (ref "U$1") (pin "INT0") (pinfunction "INT0_INT0") (pintype "bidirectional"))
    )
    (net (code "73") (name "unconnected-(U$1-PadINT1)") (class "Default")
      (node (ref "U$1") (pin "INT1") (pinfunction "INT1_INT1") (pintype "bidirectional"))
    )
    (net (code "74") (name "unconnected-(U$2-PadP$3)") (class "Default")
      (node (ref "U$2") (pin "P$3") (pinfunction "P$3_P$3") (pintype "bidirectional"))
    )
    (net (code "75") (name "unconnected-(U$3-0{slash}RX1{slash}T-Pad0)") (class "Default")
      (node (ref "U$3") (pin "0") (pinfunction "0/RX1/T_0") (pintype "bidirectional"))
    )
    (net (code "76") (name "unconnected-(U$3-1{slash}TX1{slash}T-Pad1)") (class "Default")
      (node (ref "U$3") (pin "1") (pinfunction "1/TX1/T_1") (pintype "bidirectional"))
    )
    (net (code "77") (name "unconnected-(U$3-3{slash}CAN-TX{slash}PWM-Pad3)") (class "Default")
      (node (ref "U$3") (pin "3") (pinfunction "3/CAN-TX/PWM_3") (pintype "bidirectional"))
    )
    (net (code "78") (name "unconnected-(U$3-4{slash}CAN-RX{slash}PWM-Pad4)") (class "Default")
      (node (ref "U$3") (pin "4") (pinfunction "4/CAN-RX/PWM_4") (pintype "bidirectional"))
    )
    (net (code "79") (name "unconnected-(U$3-7{slash}RX3-Pad7)") (class "Default")
      (node (ref "U$3") (pin "7") (pinfunction "7/RX3_7") (pintype "bidirectional"))
    )
    (net (code "80") (name "unconnected-(U$3-8{slash}TX3-Pad8)") (class "Default")
      (node (ref "U$3") (pin "8") (pinfunction "8/TX3_8") (pintype "bidirectional"))
    )
    (net (code "81") (name "unconnected-(U$3-10{slash}TX2{slash}PWM-Pad10)") (class "Default")
      (node (ref "U$3") (pin "10") (pinfunction "10/TX2/PWM_10") (pintype "bidirectional"))
    )
    (net (code "82") (name "unconnected-(U$4-PadP$1)") (class "Default")
      (node (ref "U$4") (pin "P$1") (pinfunction "P$1_P$1") (pintype "bidirectional"))
    )
    (net (code "83") (name "unconnected-(U$4-PadP$2)") (class "Default")
      (node (ref "U$4") (pin "P$2") (pinfunction "P$2_P$2") (pintype "bidirectional"))
    )
    (net (code "84") (name "unconnected-(U$4-PadP$3)") (class "Default")
      (node (ref "U$4") (pin "P$3") (pinfunction "P$3_P$3") (pintype "bidirectional"))
    )
    (net (code "85") (name "unconnected-(U$4-PadP$4)") (class "Default")
      (node (ref "U$4") (pin "P$4") (pinfunction "P$4_P$4") (pintype "bidirectional"))
    )
    (net (code "86") (name "unconnected-(U$4-PadP$5)") (class "Default")
      (node (ref "U$4") (pin "P$5") (pinfunction "P$5_P$5") (pintype "bidirectional"))
    )
    (net (code "87") (name "unconnected-(U$4-PadP$6)") (class "Default")
      (node (ref "U$4") (pin "P$6") (pinfunction "P$6_P$6") (pintype "bidirectional"))
    )
    (net (code "88") (name "unconnected-(U$4-PadP$7)") (class "Default")
      (node (ref "U$4") (pin "P$7") (pinfunction "P$7_P$7") (pintype "bidirectional"))
    )
    (net (code "89") (name "unconnected-(U$4-PadP$8)") (class "Default")
      (node (ref "U$4") (pin "P$8") (pinfunction "P$8_P$8") (pintype "bidirectional"))
    )
    (net (code "90") (name "unconnected-(U$4-PadP$9)") (class "Default")
      (node (ref "U$4") (pin "P$9") (pinfunction "P$9_P$9") (pintype "bidirectional"))
    )
    (net (code "91") (name "unconnected-(U$4-PadP$10)") (class "Default")
      (node (ref "U$4") (pin "P$10") (pinfunction "P$10_P$10") (pintype "bidirectional"))
    )
    (net (code "92") (name "unconnected-(U$4-PadP$11)") (class "Default")
      (node (ref "U$4") (pin "P$11") (pinfunction "P$11_P$11") (pintype "bidirectional"))
    )
    (net (code "93") (name "unconnected-(U$4-PadP$12)") (class "Default")
      (node (ref "U$4") (pin "P$12") (pinfunction "P$12_P$12") (pintype "bidirectional"))
    )
    (net (code "94") (name "unconnected-(U$5-PadP$1)") (class "Default")
      (node (ref "U$5") (pin "P$1") (pinfunction "P$1_P$1") (pintype "bidirectional"))
    )
    (net (code "95") (name "unconnected-(U$5-PadP$2)") (class "Default")
      (node (ref "U$5") (pin "P$2") (pinfunction "P$2_P$2") (pintype "bidirectional"))
    )
    (net (code "96") (name "unconnected-(U$5-PadP$3)") (class "Default")
      (node (ref "U$5") (pin "P$3") (pinfunction "P$3_P$3") (pintype "bidirectional"))
    )
    (net (code "97") (name "unconnected-(U$5-PadP$4)") (class "Default")
      (node (ref "U$5") (pin "P$4") (pinfunction "P$4_P$4") (pintype "bidirectional"))
    )
    (net (code "98") (name "unconnected-(U$5-PadP$5)") (class "Default")
      (node (ref "U$5") (pin "P$5") (pinfunction "P$5_P$5") (pintype "bidirectional"))
    )
    (net (code "99") (name "unconnected-(U$5-PadP$6)") (class "Default")
      (node (ref "U$5") (pin "P$6") (pinfunction "P$6_P$6") (pintype "bidirectional"))
    )
    (net (code "100") (name "unconnected-(U$5-PadP$7)") (class "Default")
      (node (ref "U$5") (pin "P$7") (pinfunction "P$7_P$7") (pintype "bidirectional"))
    )
    (net (code "101") (name "unconnected-(U$5-PadP$8)") (class "Default")
      (node (ref "U$5") (pin "P$8") (pinfunction "P$8_P$8") (pintype "bidirectional"))
    )
    (net (code "102") (name "unconnected-(U$5-PadP$9)") (class "Default")
      (node (ref "U$5") (pin "P$9") (pinfunction "P$9_P$9") (pintype "bidirectional"))
    )
    (net (code "103") (name "unconnected-(U$5-PadP$10)") (class "Default")
      (node (ref "U$5") (pin "P$10") (pinfunction "P$10_P$10") (pintype "bidirectional"))
    )
    (net (code "104") (name "unconnected-(U$5-PadP$11)") (class "Default")
      (node (ref "U$5") (pin "P$11") (pinfunction "P$11_P$11") (pintype "bidirectional"))
    )
    (net (code "105") (name "unconnected-(U$5-PadP$12)") (class "Default")
      (node (ref "U$5") (pin "P$12") (pinfunction "P$12_P$12") (pintype "bidirectional"))
    )
  )
)
